# PIC32.net
KiCad netlist of a schematic drawn in EAGLE
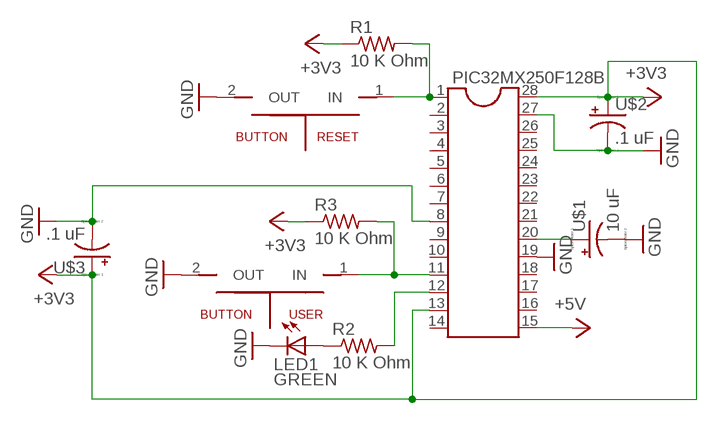
[diagram p0: schematic, sheet 1]

(export (version "E")
  (design (tool "Eeschema 10.0.6"))
  (components
    (comp (ref "LED1")
      (value "GREEN")
      (footprint "eagle-import:SMARTLED-TTW")
      (libsource (lib "eagle-import") (part "LED"))
    )
    (comp (ref "PIC32MX250F128B")
      (value "DIL28-3")
      (footprint "eagle-import:DIL28-3")
      (libsource (lib "eagle-import") (part "DIL28-3"))
    )
    (comp (ref "R1")
      (value "10 K Ohm")
      (footprint "eagle-import:0207_10")
      (libsource (lib "eagle-import") (part "R-US_0207/10"))
    )
    (comp (ref "R2")
      (value "10 K Ohm")
      (footprint "eagle-import:0207_10")
      (libsource (lib "eagle-import") (part "R-US_0207/10"))
    )
    (comp (ref "R3")
      (value "10 K Ohm")
      (footprint "eagle-import:0207_10")
      (libsource (lib "eagle-import") (part "R-US_0207/10"))
    )
    (comp (ref "RESET")
      (value "BUTTON")
      (footprint "eagle-import:BUTTON")
      (libsource (lib "eagle-import") (part "BUTTON"))
    )
    (comp (ref "U$1")
      (value "10 uF")
      (footprint "eagle-import:E2,5-5")
      (libsource (lib "eagle-import") (part "CAP-5"))
    )
    (comp (ref "U$2")
      (value ".1 uF")
      (footprint "eagle-import:E1,8-4")
      (libsource (lib "eagle-import") (part "CAP-4"))
    )
    (comp (ref "U$3")
      (value ".1 uF")
      (footprint "eagle-import:E1,8-4")
      (libsource (lib "eagle-import") (part "CAP-4"))
    )
    (comp (ref "USER")
      (value "BUTTON")
      (footprint "eagle-import:BUTTON")
      (libsource (lib "eagle-import") (part "BUTTON"))
    )
  )
  (nets
    (net (code "1") (name "+3V3") (class "Default")
      (node (ref "PIC32MX250F128B") (pin "13") (pinfunction "13_13") (pintype "passive"))
      (node (ref "PIC32MX250F128B") (pin "28") (pinfunction "28_28") (pintype "passive"))
      (node (ref "R1") (pin "1") (pinfunction "1_1") (pintype "passive"))
      (node (ref "R3") (pin "1") (pinfunction "1_1") (pintype "passive"))
      (node (ref "U$2") (pin "+") (pinfunction "+_+") (pintype "passive"))
      (node (ref "U$3") (pin "+") (pinfunction "+_+") (pintype "passive"))
    )
    (net (code "2") (name "+5V") (class "Default")
      (node (ref "PIC32MX250F128B") (pin "15") (pinfunction "15_15") (pintype "passive"))
    )
    (net (code "3") (name "GND") (class "Default")
      (node (ref "LED1") (pin "C@1") (pinfunction "C_C@1") (pintype "passive"))
      (node (ref "PIC32MX250F128B") (pin "19") (pinfunction "19_19") (pintype "passive"))
      (node (ref "PIC32MX250F128B") (pin "27") (pinfunction "27_27") (pintype "passive"))
      (node (ref "PIC32MX250F128B") (pin "8") (pinfunction "8_8") (pintype "passive"))
      (node (ref "RESET") (pin "2") (pinfunction "OUT_2") (pintype "bidirectional"))
      (node (ref "U$1") (pin "-") (pinfunction "-_-") (pintype "passive"))
      (node (ref "U$2") (pin "-") (pinfunction "-_-") (pintype "passive"))
      (node (ref "U$3") (pin "-") (pinfunction "-_-") (pintype "passive"))
      (node (ref "USER") (pin "2") (pinfunction "OUT_2") (pintype "bidirectional"))
    )
    (net (code "4") (name "Net-(LED1-A)") (class "Default")
      (node (ref "LED1") (pin "A@1") (pinfunction "A_A@1") (pintype "passive"))
      (node (ref "R2") (pin "1") (pinfunction "1_1") (pintype "passive"))
    )
    (net (code "5") (name "Net-(PIC32MX250F128B-Pad12)") (class "Default")
      (node (ref "PIC32MX250F128B") (pin "12") (pinfunction "12_12") (pintype "passive"))
      (node (ref "R2") (pin "2") (pinfunction "2_2") (pintype "passive"))
    )
    (net (code "6") (name "Net-(PIC32MX250F128B-Pad20)") (class "Default")
      (node (ref "PIC32MX250F128B") (pin "20") (pinfunction "20_20") (pintype "passive"))
      (node (ref "U$1") (pin "+") (pinfunction "+_+") (pintype "passive"))
    )
    (net (code "7") (name "Net-(RESET-IN)") (class "Default")
      (node (ref "PIC32MX250F128B") (pin "1") (pinfunction "1_1") (pintype "passive"))
      (node (ref "R1") (pin "2") (pinfunction "2_2") (pintype "passive"))
      (node (ref "RESET") (pin "1") (pinfunction "IN_1") (pintype "bidirectional"))
    )
    (net (code "8") (name "Net-(USER-IN)") (class "Default")
      (node (ref "PIC32MX250F128B") (pin "11") (pinfunction "11_11") (pintype "passive"))
      (node (ref "R3") (pin "2") (pinfunction "2_2") (pintype "passive"))
      (node (ref "USER") (pin "1") (pinfunction "IN_1") (pintype "bidirectional"))
    )
    (net (code "9") (name "unconnected-(PIC32MX250F128B-Pad2)") (class "Default")
      (node (ref "PIC32MX250F128B") (pin "2") (pinfunction "2_2") (pintype "passive"))
    )
    (net (code "10") (name "unconnected-(PIC32MX250F128B-Pad3)") (class "Default")
      (node (ref "PIC32MX250F128B") (pin "3") (pinfunction "3_3") (pintype "passive"))
    )
    (net (code "11") (name "unconnected-(PIC32MX250F128B-Pad4)") (class "Default")
      (node (ref "PIC32MX250F128B") (pin "4") (pinfunction "4_4") (pintype "passive"))
    )
    (net (code "12") (name "unconnected-(PIC32MX250F128B-Pad5)") (class "Default")
      (node (ref "PIC32MX250F128B") (pin "5") (pinfunction "5_5") (pintype "passive"))
    )
    (net (code "13") (name "unconnected-(PIC32MX250F128B-Pad6)") (class "Default")
      (node (ref "PIC32MX250F128B") (pin "6") (pinfunction "6_6") (pintype "passive"))
    )
    (net (code "14") (name "unconnected-(PIC32MX250F128B-Pad7)") (class "Default")
      (node (ref "PIC32MX250F128B") (pin "7") (pinfunction "7_7") (pintype "passive"))
    )
    (net (code "15") (name "unconnected-(PIC32MX250F128B-Pad9)") (class "Default")
      (node (ref "PIC32MX250F128B") (pin "9") (pinfunction "9_9") (pintype "passive"))
    )
    (net (code "16") (name "unconnected-(PIC32MX250F128B-Pad10)") (class "Default")
      (node (ref "PIC32MX250F128B") (pin "10") (pinfunction "10_10") (pintype "passive"))
    )
    (net (code "17") (name "unconnected-(PIC32MX250F128B-Pad14)") (class "Default")
      (node (ref "PIC32MX250F128B") (pin "14") (pinfunction "14_14") (pintype "passive"))
    )
    (net (code "18") (name "unconnected-(PIC32MX250F128B-Pad16)") (class "Default")
      (node (ref "PIC32MX250F128B") (pin "16") (pinfunction "16_16") (pintype "passive"))
    )
    (net (code "19") (name "unconnected-(PIC32MX250F128B-Pad17)") (class "Default")
      (node (ref "PIC32MX250F128B") (pin "17") (pinfunction "17_17") (pintype "passive"))
    )
    (net (code "20") (name "unconnected-(PIC32MX250F128B-Pad18)") (class "Default")
      (node (ref "PIC32MX250F128B") (pin "18") (pinfunction "18_18") (pintype "passive"))
    )
    (net (code "21") (name "unconnected-(PIC32MX250F128B-Pad21)") (class "Default")
      (node (ref "PIC32MX250F128B") (pin "21") (pinfunction "21_21") (pintype "passive"))
    )
    (net (code "22") (name "unconnected-(PIC32MX250F128B-Pad22)") (class "Default")
      (node (ref "PIC32MX250F128B") (pin "22") (pinfunction "22_22") (pintype "passive"))
    )
    (net (code "23") (name "unconnected-(PIC32MX250F128B-Pad23)") (class "Default")
      (node (ref "PIC32MX250F128B") (pin "23") (pinfunction "23_23") (pintype "passive"))
    )
    (net (code "24") (name "unconnected-(PIC32MX250F128B-Pad24)") (class "Default")
      (node (ref "PIC32MX250F128B") (pin "24") (pinfunction "24_24") (pintype "passive"))
    )
    (net (code "25") (name "unconnected-(PIC32MX250F128B-Pad25)") (class "Default")
      (node (ref "PIC32MX250F128B") (pin "25") (pinfunction "25_25") (pintype "passive"))
    )
    (net (code "26") (name "unconnected-(PIC32MX250F128B-Pad26)") (class "Default")
      (node (ref "PIC32MX250F128B") (pin "26") (pinfunction "26_26") (pintype "passive"))
    )
  )
)
